# P07_F28379D-PWR.net
KiCad netlist of a schematic drawn in Altium Designer
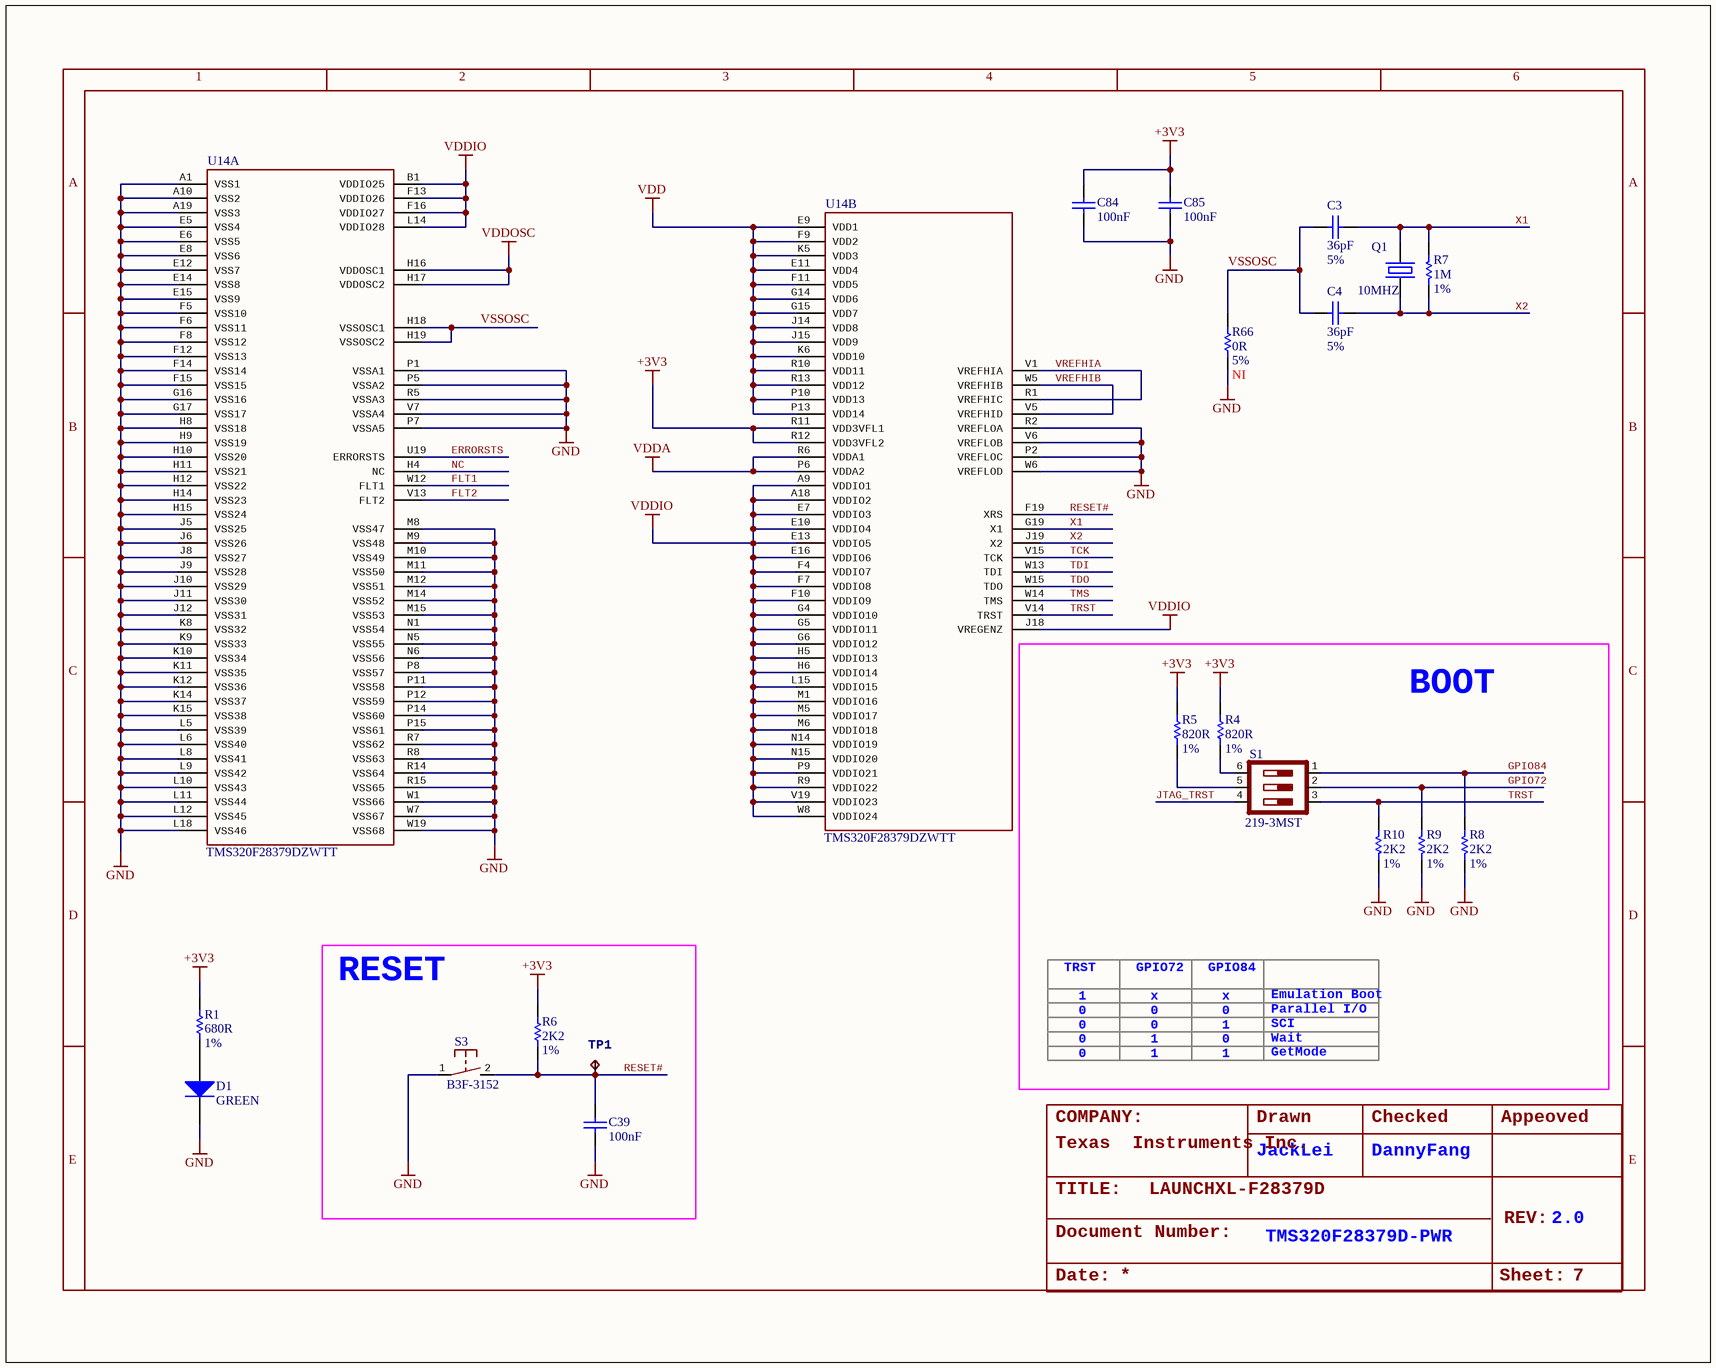
[diagram p0: P07_F28379D-PWR.SchDoc]

(export (version "E")
  (design (tool "Eeschema 10.0.6"))
  (components
    (comp (ref "C3")
      (value "36pF")
      (footprint "C0402")
      (description "CAP,36pF,+/-5%,C0G,50V,SMD0402")
      (fields
        (field (name "RATING") "5%")
        (field (name "MANUFACTURER") "MURATA")
        (field (name "MANUFACTURER PART NUMBER") "GRM1555C1H360JA01D")
      )
      (libsource (lib "Embest") (part "C"))
    )
    (comp (ref "C4")
      (value "36pF")
      (footprint "C0402")
      (description "CAP,36pF,+/-5%,C0G,50V,SMD0402")
      (fields
        (field (name "RATING") "5%")
        (field (name "MANUFACTURER") "MURATA")
        (field (name "MANUFACTURER PART NUMBER") "GRM1555C1H360JA01D")
      )
      (libsource (lib "Embest") (part "C"))
    )
    (comp (ref "C39")
      (value "100nF")
      (footprint "C0402")
      (description "CAP,100NF(0.1uf),+/-10%,X5R,10V,SMD0402")
      (fields
        (field (name "MANUFACTURER") "MURATA")
        (field (name "MANUFACTURER PART NUMBER") "GRM155R61A104KA01D")
      )
      (libsource (lib "Embest") (part "C"))
    )
    (comp (ref "C84")
      (value "100nF")
      (footprint "C0402")
      (description "CAP,100NF(0.1uf),+/-10%,X5R,10V,SMD0402")
      (fields
        (field (name "MANUFACTURER") "MURATA")
        (field (name "MANUFACTURER PART NUMBER") "GRM155R61A104KA01D")
      )
      (libsource (lib "Embest") (part "C"))
    )
    (comp (ref "C85")
      (value "100nF")
      (footprint "C0402")
      (description "CAP,100NF(0.1uf),+/-10%,X5R,10V,SMD0402")
      (fields
        (field (name "MANUFACTURER") "MURATA")
        (field (name "MANUFACTURER PART NUMBER") "GRM155R61A104KA01D")
      )
      (libsource (lib "Embest") (part "C"))
    )
    (comp (ref "D1")
      (value "GREEN")
      (footprint "D0805")
      (description "LED, Bright GREEN , 570nm,30mA,SMD,0805")
      (fields (field (name "MANUFACTURER") "WURTH") (field (name "MANUFACTURER PART NUMBER") "150080VS75000"))
      (libsource (lib "Embest") (part "D"))
    )
    (comp (ref "Q1")
      (value "10MHZ")
      (footprint "OSC488P1105X465X350-2N")
      (description "Crystal 10.0000MHz 30ppm 18pF 60 Ohm -40°C - 85°C Through Hole HC49/US")
      (fields (field (name "MANUFACTURER") "CTS") (field (name "MANUFACTURER PART NUMBER") "ATS100B-E"))
      (libsource (lib "Embest") (part "X"))
    )
    (comp (ref "R1")
      (value "680R")
      (footprint "R0402")
      (description "RES,680R,+/-1%,1/16W,SMD0402")
      (fields
        (field (name "RATING") "1%")
        (field (name "MANUFACTURER") "YAGEO")
        (field (name "MANUFACTURER PART NUMBER") "RC0402FR-07680RL")
      )
      (libsource (lib "Embest") (part "R"))
    )
    (comp (ref "R4")
      (value "820R")
      (footprint "R0402")
      (description "RES,820R,+/-1%,1/16W,SMD0402")
      (fields
        (field (name "RATING") "1%")
        (field (name "MANUFACTURER") "YAGEO")
        (field (name "MANUFACTURER PART NUMBER") "RC0402FR-07820RL")
      )
      (libsource (lib "Embest") (part "R"))
    )
    (comp (ref "R5")
      (value "820R")
      (footprint "R0402")
      (description "RES,820R,+/-1%,1/16W,SMD0402")
      (fields
        (field (name "RATING") "1%")
        (field (name "MANUFACTURER") "YAGEO")
        (field (name "MANUFACTURER PART NUMBER") "RC0402FR-07820RL")
      )
      (libsource (lib "Embest") (part "R"))
    )
    (comp (ref "R6")
      (value "2K2")
      (footprint "R0402")
      (description "RES,2K2,+/-1%,1/16W,SMD0402")
      (fields
        (field (name "RATING") "1%")
        (field (name "MANUFACTURER") "YAGEO")
        (field (name "MANUFACTURER PART NUMBER") "RC0402FR-072K2L")
      )
      (libsource (lib "Embest") (part "R"))
    )
    (comp (ref "R7")
      (value "1M")
      (footprint "R0402")
      (description "RES,1M,+/-1%,1/16W,SMD0402")
      (fields
        (field (name "RATING") "1%")
        (field (name "MANUFACTURER") "YAGEO")
        (field (name "MANUFACTURER PART NUMBER") "RC0402FR-071ML")
      )
      (libsource (lib "Embest") (part "R"))
    )
    (comp (ref "R8")
      (value "2K2")
      (footprint "R0402")
      (description "RES,2K2,+/-1%,1/16W,SMD0402")
      (fields
        (field (name "RATING") "1%")
        (field (name "MANUFACTURER") "YAGEO")
        (field (name "MANUFACTURER PART NUMBER") "RC0402FR-072K2L")
      )
      (libsource (lib "Embest") (part "R"))
    )
    (comp (ref "R9")
      (value "2K2")
      (footprint "R0402")
      (description "RES,2K2,+/-1%,1/16W,SMD0402")
      (fields
        (field (name "RATING") "1%")
        (field (name "MANUFACTURER") "YAGEO")
        (field (name "MANUFACTURER PART NUMBER") "RC0402FR-072K2L")
      )
      (libsource (lib "Embest") (part "R"))
    )
    (comp (ref "R10")
      (value "2K2")
      (footprint "R0402")
      (description "RES,2K2,+/-1%,1/16W,SMD0402")
      (fields
        (field (name "RATING") "1%")
        (field (name "MANUFACTURER") "YAGEO")
        (field (name "MANUFACTURER PART NUMBER") "RC0402FR-072K2L")
      )
      (libsource (lib "Embest") (part "R"))
    )
    (comp (ref "R66")
      (value "0R")
      (footprint "R0402")
      (description "RES,0R,+/-5%,1/16W,SMD0402")
      (fields
        (field (name "RATING") "5%")
        (field (name "ASSY") "NI")
        (field (name "MANUFACTURER") "YAGEO")
        (field (name "MANUFACTURER PART NUMBER") "RC0402JR-070RL")
      )
      (libsource (lib "Embest") (part "R"))
    )
    (comp (ref "S1")
      (value "219-3MST")
      (footprint "SW254P990X385-6N")
      (description "Switch, DIP Switches,3 Position,2.54MM Pitch,black housing,white plunger,SMD")
      (fields (field (name "MANUFACTURER") "CTS"))
      (libsource (lib "Embest") (part "SW6"))
    )
    (comp (ref "S3")
      (value "B3F-3152")
      (footprint "SW4P730X625")
      (description "SWITCH TACTILE SPST-NO 0.05A 24V")
      (fields (field (name "MANUFACTURER") "OMRON"))
      (libsource (lib "Embest") (part "SW2_2"))
    )
    (comp (ref "TP1")
      (value "TESTPAD_TPB1,27")
      (footprint "TESTPAD_B1,27")
      (description "Test pad")
      (libsource (lib "Embest") (part "TESTPAD_TPB1,27"))
    )
    (comp (ref "U14")
      (value "TMS320F28379DZWTT")
      (footprint "BGA337C80P19X19_1600X1600X140")
      (description "IC, MCU 32BIT 1024KB,TMS320F28379DZWTT,BGA-337,SMD,customer supply")
      (fields (field (name "MANUFACTURER") "TI"))
      (libsource (lib "Embest") (part "TMS320F28379DZWTT"))
    )
  )
  (nets
    (net (code "1") (name "+3V3") (class "Default")
      (node (ref "C84") (pin "1") (pinfunction "1_1") (pintype "passive"))
      (node (ref "C85") (pin "1") (pinfunction "1_1") (pintype "passive"))
      (node (ref "R1") (pin "2") (pinfunction "2_2") (pintype "passive"))
      (node (ref "R4") (pin "2") (pinfunction "2_2") (pintype "passive"))
      (node (ref "R5") (pin "2") (pinfunction "2_2") (pintype "passive"))
      (node (ref "R6") (pin "2") (pinfunction "2_2") (pintype "passive"))
      (node (ref "U14") (pin "R11") (pinfunction "VDD3VFL1_R11") (pintype "passive"))
      (node (ref "U14") (pin "R12") (pinfunction "VDD3VFL2_R12") (pintype "passive"))
    )
    (net (code "2") (name "/ERRORSTS") (class "Default")
      (node (ref "U14") (pin "U19") (pinfunction "ERRORSTS_U19") (pintype "passive"))
    )
    (net (code "3") (name "/FLT1") (class "Default")
      (node (ref "U14") (pin "W12") (pinfunction "FLT1_W12") (pintype "passive"))
    )
    (net (code "4") (name "/FLT2") (class "Default")
      (node (ref "U14") (pin "V13") (pinfunction "FLT2_V13") (pintype "passive"))
    )
    (net (code "5") (name "/GPIO72") (class "Default")
      (node (ref "R9") (pin "2") (pinfunction "2_2") (pintype "passive"))
      (node (ref "S1") (pin "2") (pinfunction "2_2") (pintype "passive"))
    )
    (net (code "6") (name "/GPIO84") (class "Default")
      (node (ref "R8") (pin "2") (pinfunction "2_2") (pintype "passive"))
      (node (ref "S1") (pin "1") (pinfunction "1_1") (pintype "passive"))
    )
    (net (code "7") (name "/JTAG_TRST") (class "Default")
      (node (ref "S1") (pin "4") (pinfunction "4_4") (pintype "passive"))
    )
    (net (code "8") (name "/NC") (class "Default")
      (node (ref "U14") (pin "H4") (pinfunction "NC_H4") (pintype "passive"))
    )
    (net (code "9") (name "/RESET#") (class "Default")
      (node (ref "C39") (pin "1") (pinfunction "1_1") (pintype "passive"))
      (node (ref "R6") (pin "1") (pinfunction "1_1") (pintype "passive"))
      (node (ref "S3") (pin "2") (pinfunction "S_2") (pintype "passive"))
      (node (ref "TP1") (pin "TP") (pinfunction "TP_TP") (pintype "passive"))
      (node (ref "U14") (pin "F19") (pinfunction "XRS_F19") (pintype "passive"))
    )
    (net (code "10") (name "/TCK") (class "Default")
      (node (ref "U14") (pin "V15") (pinfunction "TCK_V15") (pintype "passive"))
    )
    (net (code "11") (name "/TDI") (class "Default")
      (node (ref "U14") (pin "W13") (pinfunction "TDI_W13") (pintype "passive"))
    )
    (net (code "12") (name "/TDO") (class "Default")
      (node (ref "U14") (pin "W15") (pinfunction "TDO_W15") (pintype "passive"))
    )
    (net (code "13") (name "/TMS") (class "Default")
      (node (ref "U14") (pin "W14") (pinfunction "TMS_W14") (pintype "passive"))
    )
    (net (code "14") (name "/TRST") (class "Default")
      (node (ref "R10") (pin "2") (pinfunction "2_2") (pintype "passive"))
      (node (ref "S1") (pin "3") (pinfunction "3_3") (pintype "passive"))
      (node (ref "U14") (pin "V14") (pinfunction "TRST_V14") (pintype "passive"))
    )
    (net (code "15") (name "/VREFHIA") (class "Default")
      (node (ref "U14") (pin "R1") (pinfunction "VREFHIC_R1") (pintype "passive"))
      (node (ref "U14") (pin "V1") (pinfunction "VREFHIA_V1") (pintype "passive"))
    )
    (net (code "16") (name "/VREFHIB") (class "Default")
      (node (ref "U14") (pin "V5") (pinfunction "VREFHID_V5") (pintype "passive"))
      (node (ref "U14") (pin "W5") (pinfunction "VREFHIB_W5") (pintype "passive"))
    )
    (net (code "17") (name "/VSSOSC") (class "Default")
      (node (ref "C3") (pin "2") (pinfunction "2_2") (pintype "passive"))
      (node (ref "C4") (pin "2") (pinfunction "2_2") (pintype "passive"))
      (node (ref "R66") (pin "1") (pinfunction "1_1") (pintype "passive"))
      (node (ref "U14") (pin "H18") (pinfunction "VSSOSC1_H18") (pintype "passive"))
      (node (ref "U14") (pin "H19") (pinfunction "VSSOSC2_H19") (pintype "passive"))
    )
    (net (code "18") (name "/X1") (class "Default")
      (node (ref "C3") (pin "1") (pinfunction "1_1") (pintype "passive"))
      (node (ref "Q1") (pin "2") (pinfunction "2_2") (pintype "passive"))
      (node (ref "R7") (pin "2") (pinfunction "2_2") (pintype "passive"))
      (node (ref "U14") (pin "G19") (pinfunction "X1_G19") (pintype "passive"))
    )
    (net (code "19") (name "/X2") (class "Default")
      (node (ref "C4") (pin "1") (pinfunction "1_1") (pintype "passive"))
      (node (ref "Q1") (pin "1") (pinfunction "1_1") (pintype "passive"))
      (node (ref "R7") (pin "1") (pinfunction "1_1") (pintype "passive"))
      (node (ref "U14") (pin "J19") (pinfunction "X2_J19") (pintype "passive"))
    )
    (net (code "20") (name "GND") (class "Default")
      (node (ref "C39") (pin "2") (pinfunction "2_2") (pintype "passive"))
      (node (ref "C84") (pin "2") (pinfunction "2_2") (pintype "passive"))
      (node (ref "C85") (pin "2") (pinfunction "2_2") (pintype "passive"))
      (node (ref "D1") (pin "1") (pinfunction "1_1") (pintype "passive"))
      (node (ref "R10") (pin "1") (pinfunction "1_1") (pintype "passive"))
      (node (ref "R66") (pin "2") (pinfunction "2_2") (pintype "passive"))
      (node (ref "R8") (pin "1") (pinfunction "1_1") (pintype "passive"))
      (node (ref "R9") (pin "1") (pinfunction "1_1") (pintype "passive"))
      (node (ref "S3") (pin "1") (pinfunction "P_1") (pintype "passive"))
      (node (ref "U14") (pin "A1") (pinfunction "VSS1_A1") (pintype "passive"))
      (node (ref "U14") (pin "A10") (pinfunction "VSS2_A10") (pintype "passive"))
      (node (ref "U14") (pin "A19") (pinfunction "VSS3_A19") (pintype "passive"))
      (node (ref "U14") (pin "E12") (pinfunction "VSS7_E12") (pintype "passive"))
      (node (ref "U14") (pin "E14") (pinfunction "VSS8_E14") (pintype "passive"))
      (node (ref "U14") (pin "E15") (pinfunction "VSS9_E15") (pintype "passive"))
      (node (ref "U14") (pin "E5") (pinfunction "VSS4_E5") (pintype "passive"))
      (node (ref "U14") (pin "E6") (pinfunction "VSS5_E6") (pintype "passive"))
      (node (ref "U14") (pin "E8") (pinfunction "VSS6_E8") (pintype "passive"))
      (node (ref "U14") (pin "F12") (pinfunction "VSS13_F12") (pintype "passive"))
      (node (ref "U14") (pin "F14") (pinfunction "VSS14_F14") (pintype "passive"))
      (node (ref "U14") (pin "F15") (pinfunction "VSS15_F15") (pintype "passive"))
      (node (ref "U14") (pin "F5") (pinfunction "VSS10_F5") (pintype "passive"))
      (node (ref "U14") (pin "F6") (pinfunction "VSS11_F6") (pintype "passive"))
      (node (ref "U14") (pin "F8") (pinfunction "VSS12_F8") (pintype "passive"))
      (node (ref "U14") (pin "G16") (pinfunction "VSS16_G16") (pintype "passive"))
      (node (ref "U14") (pin "G17") (pinfunction "VSS17_G17") (pintype "passive"))
      (node (ref "U14") (pin "H10") (pinfunction "VSS20_H10") (pintype "passive"))
      (node (ref "U14") (pin "H11") (pinfunction "VSS21_H11") (pintype "passive"))
      (node (ref "U14") (pin "H12") (pinfunction "VSS22_H12") (pintype "passive"))
      (node (ref "U14") (pin "H14") (pinfunction "VSS23_H14") (pintype "passive"))
      (node (ref "U14") (pin "H15") (pinfunction "VSS24_H15") (pintype "passive"))
      (node (ref "U14") (pin "H8") (pinfunction "VSS18_H8") (pintype "passive"))
      (node (ref "U14") (pin "H9") (pinfunction "VSS19_H9") (pintype "passive"))
      (node (ref "U14") (pin "J10") (pinfunction "VSS29_J10") (pintype "passive"))
      (node (ref "U14") (pin "J11") (pinfunction "VSS30_J11") (pintype "passive"))
      (node (ref "U14") (pin "J12") (pinfunction "VSS31_J12") (pintype "passive"))
      (node (ref "U14") (pin "J5") (pinfunction "VSS25_J5") (pintype "passive"))
      (node (ref "U14") (pin "J6") (pinfunction "VSS26_J6") (pintype "passive"))
      (node (ref "U14") (pin "J8") (pinfunction "VSS27_J8") (pintype "passive"))
      (node (ref "U14") (pin "J9") (pinfunction "VSS28_J9") (pintype "passive"))
      (node (ref "U14") (pin "K10") (pinfunction "VSS34_K10") (pintype "passive"))
      (node (ref "U14") (pin "K11") (pinfunction "VSS35_K11") (pintype "passive"))
      (node (ref "U14") (pin "K12") (pinfunction "VSS36_K12") (pintype "passive"))
      (node (ref "U14") (pin "K14") (pinfunction "VSS37_K14") (pintype "passive"))
      (node (ref "U14") (pin "K15") (pinfunction "VSS38_K15") (pintype "passive"))
      (node (ref "U14") (pin "K8") (pinfunction "VSS32_K8") (pintype "passive"))
      (node (ref "U14") (pin "K9") (pinfunction "VSS33_K9") (pintype "passive"))
      (node (ref "U14") (pin "L10") (pinfunction "VSS43_L10") (pintype "passive"))
      (node (ref "U14") (pin "L11") (pinfunction "VSS44_L11") (pintype "passive"))
      (node (ref "U14") (pin "L12") (pinfunction "VSS45_L12") (pintype "passive"))
      (node (ref "U14") (pin "L18") (pinfunction "VSS46_L18") (pintype "passive"))
      (node (ref "U14") (pin "L5") (pinfunction "VSS39_L5") (pintype "passive"))
      (node (ref "U14") (pin "L6") (pinfunction "VSS40_L6") (pintype "passive"))
      (node (ref "U14") (pin "L8") (pinfunction "VSS41_L8") (pintype "passive"))
      (node (ref "U14") (pin "L9") (pinfunction "VSS42_L9") (pintype "passive"))
      (node (ref "U14") (pin "M10") (pinfunction "VSS49_M10") (pintype "passive"))
      (node (ref "U14") (pin "M11") (pinfunction "VSS50_M11") (pintype "passive"))
      (node (ref "U14") (pin "M12") (pinfunction "VSS51_M12") (pintype "passive"))
      (node (ref "U14") (pin "M14") (pinfunction "VSS52_M14") (pintype "passive"))
      (node (ref "U14") (pin "M15") (pinfunction "VSS53_M15") (pintype "passive"))
      (node (ref "U14") (pin "M8") (pinfunction "VSS47_M8") (pintype "passive"))
      (node (ref "U14") (pin "M9") (pinfunction "VSS48_M9") (pintype "passive"))
      (node (ref "U14") (pin "N1") (pinfunction "VSS54_N1") (pintype "passive"))
      (node (ref "U14") (pin "N5") (pinfunction "VSS55_N5") (pintype "passive"))
      (node (ref "U14") (pin "N6") (pinfunction "VSS56_N6") (pintype "passive"))
      (node (ref "U14") (pin "P1") (pinfunction "VSSA1_P1") (pintype "passive"))
      (node (ref "U14") (pin "P11") (pinfunction "VSS58_P11") (pintype "passive"))
      (node (ref "U14") (pin "P12") (pinfunction "VSS59_P12") (pintype "passive"))
      (node (ref "U14") (pin "P14") (pinfunction "VSS60_P14") (pintype "passive"))
      (node (ref "U14") (pin "P15") (pinfunction "VSS61_P15") (pintype "passive"))
      (node (ref "U14") (pin "P2") (pinfunction "VREFLOC_P2") (pintype "passive"))
      (node (ref "U14") (pin "P5") (pinfunction "VSSA2_P5") (pintype "passive"))
      (node (ref "U14") (pin "P7") (pinfunction "VSSA5_P7") (pintype "passive"))
      (node (ref "U14") (pin "P8") (pinfunction "VSS57_P8") (pintype "passive"))
      (node (ref "U14") (pin "R14") (pinfunction "VSS64_R14") (pintype "passive"))
      (node (ref "U14") (pin "R15") (pinfunction "VSS65_R15") (pintype "passive"))
      (node (ref "U14") (pin "R2") (pinfunction "VREFLOA_R2") (pintype "passive"))
      (node (ref "U14") (pin "R5") (pinfunction "VSSA3_R5") (pintype "passive"))
      (node (ref "U14") (pin "R7") (pinfunction "VSS62_R7") (pintype "passive"))
      (node (ref "U14") (pin "R8") (pinfunction "VSS63_R8") (pintype "passive"))
      (node (ref "U14") (pin "V6") (pinfunction "VREFLOB_V6") (pintype "passive"))
      (node (ref "U14") (pin "V7") (pinfunction "VSSA4_V7") (pintype "passive"))
      (node (ref "U14") (pin "W1") (pinfunction "VSS66_W1") (pintype "passive"))
      (node (ref "U14") (pin "W19") (pinfunction "VSS68_W19") (pintype "passive"))
      (node (ref "U14") (pin "W6") (pinfunction "VREFLOD_W6") (pintype "passive"))
      (node (ref "U14") (pin "W7") (pinfunction "VSS67_W7") (pintype "passive"))
    )
    (net (code "21") (name "Net-(D1-Pad2)") (class "Default")
      (node (ref "D1") (pin "2") (pinfunction "2_2") (pintype "passive"))
      (node (ref "R1") (pin "1") (pinfunction "1_1") (pintype "passive"))
    )
    (net (code "22") (name "Net-(R4-Pad1)") (class "Default")
      (node (ref "R4") (pin "1") (pinfunction "1_1") (pintype "passive"))
      (node (ref "S1") (pin "6") (pinfunction "6_6") (pintype "passive"))
    )
    (net (code "23") (name "Net-(R5-Pad1)") (class "Default")
      (node (ref "R5") (pin "1") (pinfunction "1_1") (pintype "passive"))
      (node (ref "S1") (pin "5") (pinfunction "5_5") (pintype "passive"))
    )
    (net (code "24") (name "VDD") (class "Default")
      (node (ref "U14") (pin "E11") (pinfunction "VDD4_E11") (pintype "passive"))
      (node (ref "U14") (pin "E9") (pinfunction "VDD1_E9") (pintype "passive"))
      (node (ref "U14") (pin "F11") (pinfunction "VDD5_F11") (pintype "passive"))
      (node (ref "U14") (pin "F9") (pinfunction "VDD2_F9") (pintype "passive"))
      (node (ref "U14") (pin "G14") (pinfunction "VDD6_G14") (pintype "passive"))
      (node (ref "U14") (pin "G15") (pinfunction "VDD7_G15") (pintype "passive"))
      (node (ref "U14") (pin "J14") (pinfunction "VDD8_J14") (pintype "passive"))
      (node (ref "U14") (pin "J15") (pinfunction "VDD9_J15") (pintype "passive"))
      (node (ref "U14") (pin "K5") (pinfunction "VDD3_K5") (pintype "passive"))
      (node (ref "U14") (pin "K6") (pinfunction "VDD10_K6") (pintype "passive"))
      (node (ref "U14") (pin "P10") (pinfunction "VDD13_P10") (pintype "passive"))
      (node (ref "U14") (pin "P13") (pinfunction "VDD14_P13") (pintype "passive"))
      (node (ref "U14") (pin "R10") (pinfunction "VDD11_R10") (pintype "passive"))
      (node (ref "U14") (pin "R13") (pinfunction "VDD12_R13") (pintype "passive"))
    )
    (net (code "25") (name "VDDA") (class "Default")
      (node (ref "U14") (pin "P6") (pinfunction "VDDA2_P6") (pintype "passive"))
      (node (ref "U14") (pin "R6") (pinfunction "VDDA1_R6") (pintype "passive"))
    )
    (net (code "26") (name "VDDIO") (class "Default")
      (node (ref "U14") (pin "A18") (pinfunction "VDDIO2_A18") (pintype "passive"))
      (node (ref "U14") (pin "A9") (pinfunction "VDDIO1_A9") (pintype "passive"))
      (node (ref "U14") (pin "B1") (pinfunction "VDDIO25_B1") (pintype "passive"))
      (node (ref "U14") (pin "E10") (pinfunction "VDDIO4_E10") (pintype "passive"))
      (node (ref "U14") (pin "E13") (pinfunction "VDDIO5_E13") (pintype "passive"))
      (node (ref "U14") (pin "E16") (pinfunction "VDDIO6_E16") (pintype "passive"))
      (node (ref "U14") (pin "E7") (pinfunction "VDDIO3_E7") (pintype "passive"))
      (node (ref "U14") (pin "F10") (pinfunction "VDDIO9_F10") (pintype "passive"))
      (node (ref "U14") (pin "F13") (pinfunction "VDDIO26_F13") (pintype "passive"))
      (node (ref "U14") (pin "F16") (pinfunction "VDDIO27_F16") (pintype "passive"))
      (node (ref "U14") (pin "F4") (pinfunction "VDDIO7_F4") (pintype "passive"))
      (node (ref "U14") (pin "F7") (pinfunction "VDDIO8_F7") (pintype "passive"))
      (node (ref "U14") (pin "G4") (pinfunction "VDDIO10_G4") (pintype "passive"))
      (node (ref "U14") (pin "G5") (pinfunction "VDDIO11_G5") (pintype "passive"))
      (node (ref "U14") (pin "G6") (pinfunction "VDDIO12_G6") (pintype "passive"))
      (node (ref "U14") (pin "H5") (pinfunction "VDDIO13_H5") (pintype "passive"))
      (node (ref "U14") (pin "H6") (pinfunction "VDDIO14_H6") (pintype "passive"))
      (node (ref "U14") (pin "J18") (pinfunction "VREGENZ_J18") (pintype "passive"))
      (node (ref "U14") (pin "L14") (pinfunction "VDDIO28_L14") (pintype "passive"))
      (node (ref "U14") (pin "L15") (pinfunction "VDDIO15_L15") (pintype "passive"))
      (node (ref "U14") (pin "M1") (pinfunction "VDDIO16_M1") (pintype "passive"))
      (node (ref "U14") (pin "M5") (pinfunction "VDDIO17_M5") (pintype "passive"))
      (node (ref "U14") (pin "M6") (pinfunction "VDDIO18_M6") (pintype "passive"))
      (node (ref "U14") (pin "N14") (pinfunction "VDDIO19_N14") (pintype "passive"))
      (node (ref "U14") (pin "N15") (pinfunction "VDDIO20_N15") (pintype "passive"))
      (node (ref "U14") (pin "P9") (pinfunction "VDDIO21_P9") (pintype "passive"))
      (node (ref "U14") (pin "R9") (pinfunction "VDDIO22_R9") (pintype "passive"))
      (node (ref "U14") (pin "V19") (pinfunction "VDDIO23_V19") (pintype "passive"))
      (node (ref "U14") (pin "W8") (pinfunction "VDDIO24_W8") (pintype "passive"))
    )
    (net (code "27") (name "VDDOSC") (class "Default")
      (node (ref "U14") (pin "H16") (pinfunction "VDDOSC1_H16") (pintype "passive"))
      (node (ref "U14") (pin "H17") (pinfunction "VDDOSC2_H17") (pintype "passive"))
    )
  )
)
